# TempSensor1.net
KiCad netlist of a schematic drawn in Altium Designer
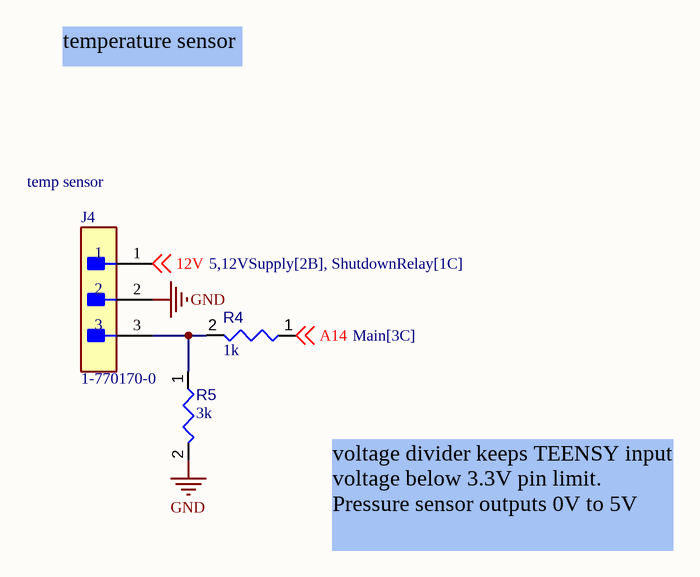
[diagram p0: TempSensor1.SchDoc]

(export (version "E")
  (design (tool "Eeschema 10.0.6"))
  (components
    (comp (ref "J4")
      (value "1-770170-0")
      (footprint "FP-1-770170-0-MFG")
      (description "CONN HEADER VERT 3POS 4.14MM")
      (fields
        (field (name "OCTOPART") "https://octopart.com/1-770170-0-te+connectivity-46505214")
        (field (name "MANUFACTURER") "TE Connectivity")
      )
      (libsource (lib "Altium Content Vault") (part "0d3f023dd272f625e17a2be33dea85f"))
    )
    (comp (ref "R4")
      (value "1k")
      (footprint "RESC0402(1005)_L")
      (description "1K 0.063W 5% 0402 (1005 Metric)  SMD")
      (fields (field (name "POWER") "63mW") (field (name "TOLERANCE") "5%"))
      (libsource (lib "Alt_ium Course") (part "1KR2J"))
    )
    (comp (ref "R5")
      (value "3k")
      (footprint "RESC0402(1005)_L")
      (description "3K 0.063W 1% 0402 (1005 Metric)  SMD")
      (fields (field (name "POWER") "63mW") (field (name "TOLERANCE") "1%"))
      (libsource (lib "Alt_ium Course") (part "3KR2F"))
    )
  )
  (nets
    (net (code "1") (name "12V") (class "Default")
      (node (ref "J4") (pin "1") (pinfunction "1_1") (pintype "passive"))
    )
    (net (code "2") (name "A14") (class "Default")
      (node (ref "R4") (pin "1") (pinfunction "1_1") (pintype "passive"))
    )
    (net (code "3") (name "GND") (class "Default")
      (node (ref "J4") (pin "2") (pinfunction "2_2") (pintype "passive"))
      (node (ref "R5") (pin "2") (pinfunction "2_2") (pintype "passive"))
    )
    (net (code "4") (name "Net-(J4-Pad3)") (class "Default")
      (node (ref "J4") (pin "3") (pinfunction "3_3") (pintype "passive"))
      (node (ref "R4") (pin "2") (pinfunction "2_2") (pintype "passive"))
      (node (ref "R5") (pin "1") (pinfunction "1_1") (pintype "passive"))
    )
  )
)
